# Pr_tica-10.net
KiCad netlist of a schematic drawn in EasyEDA
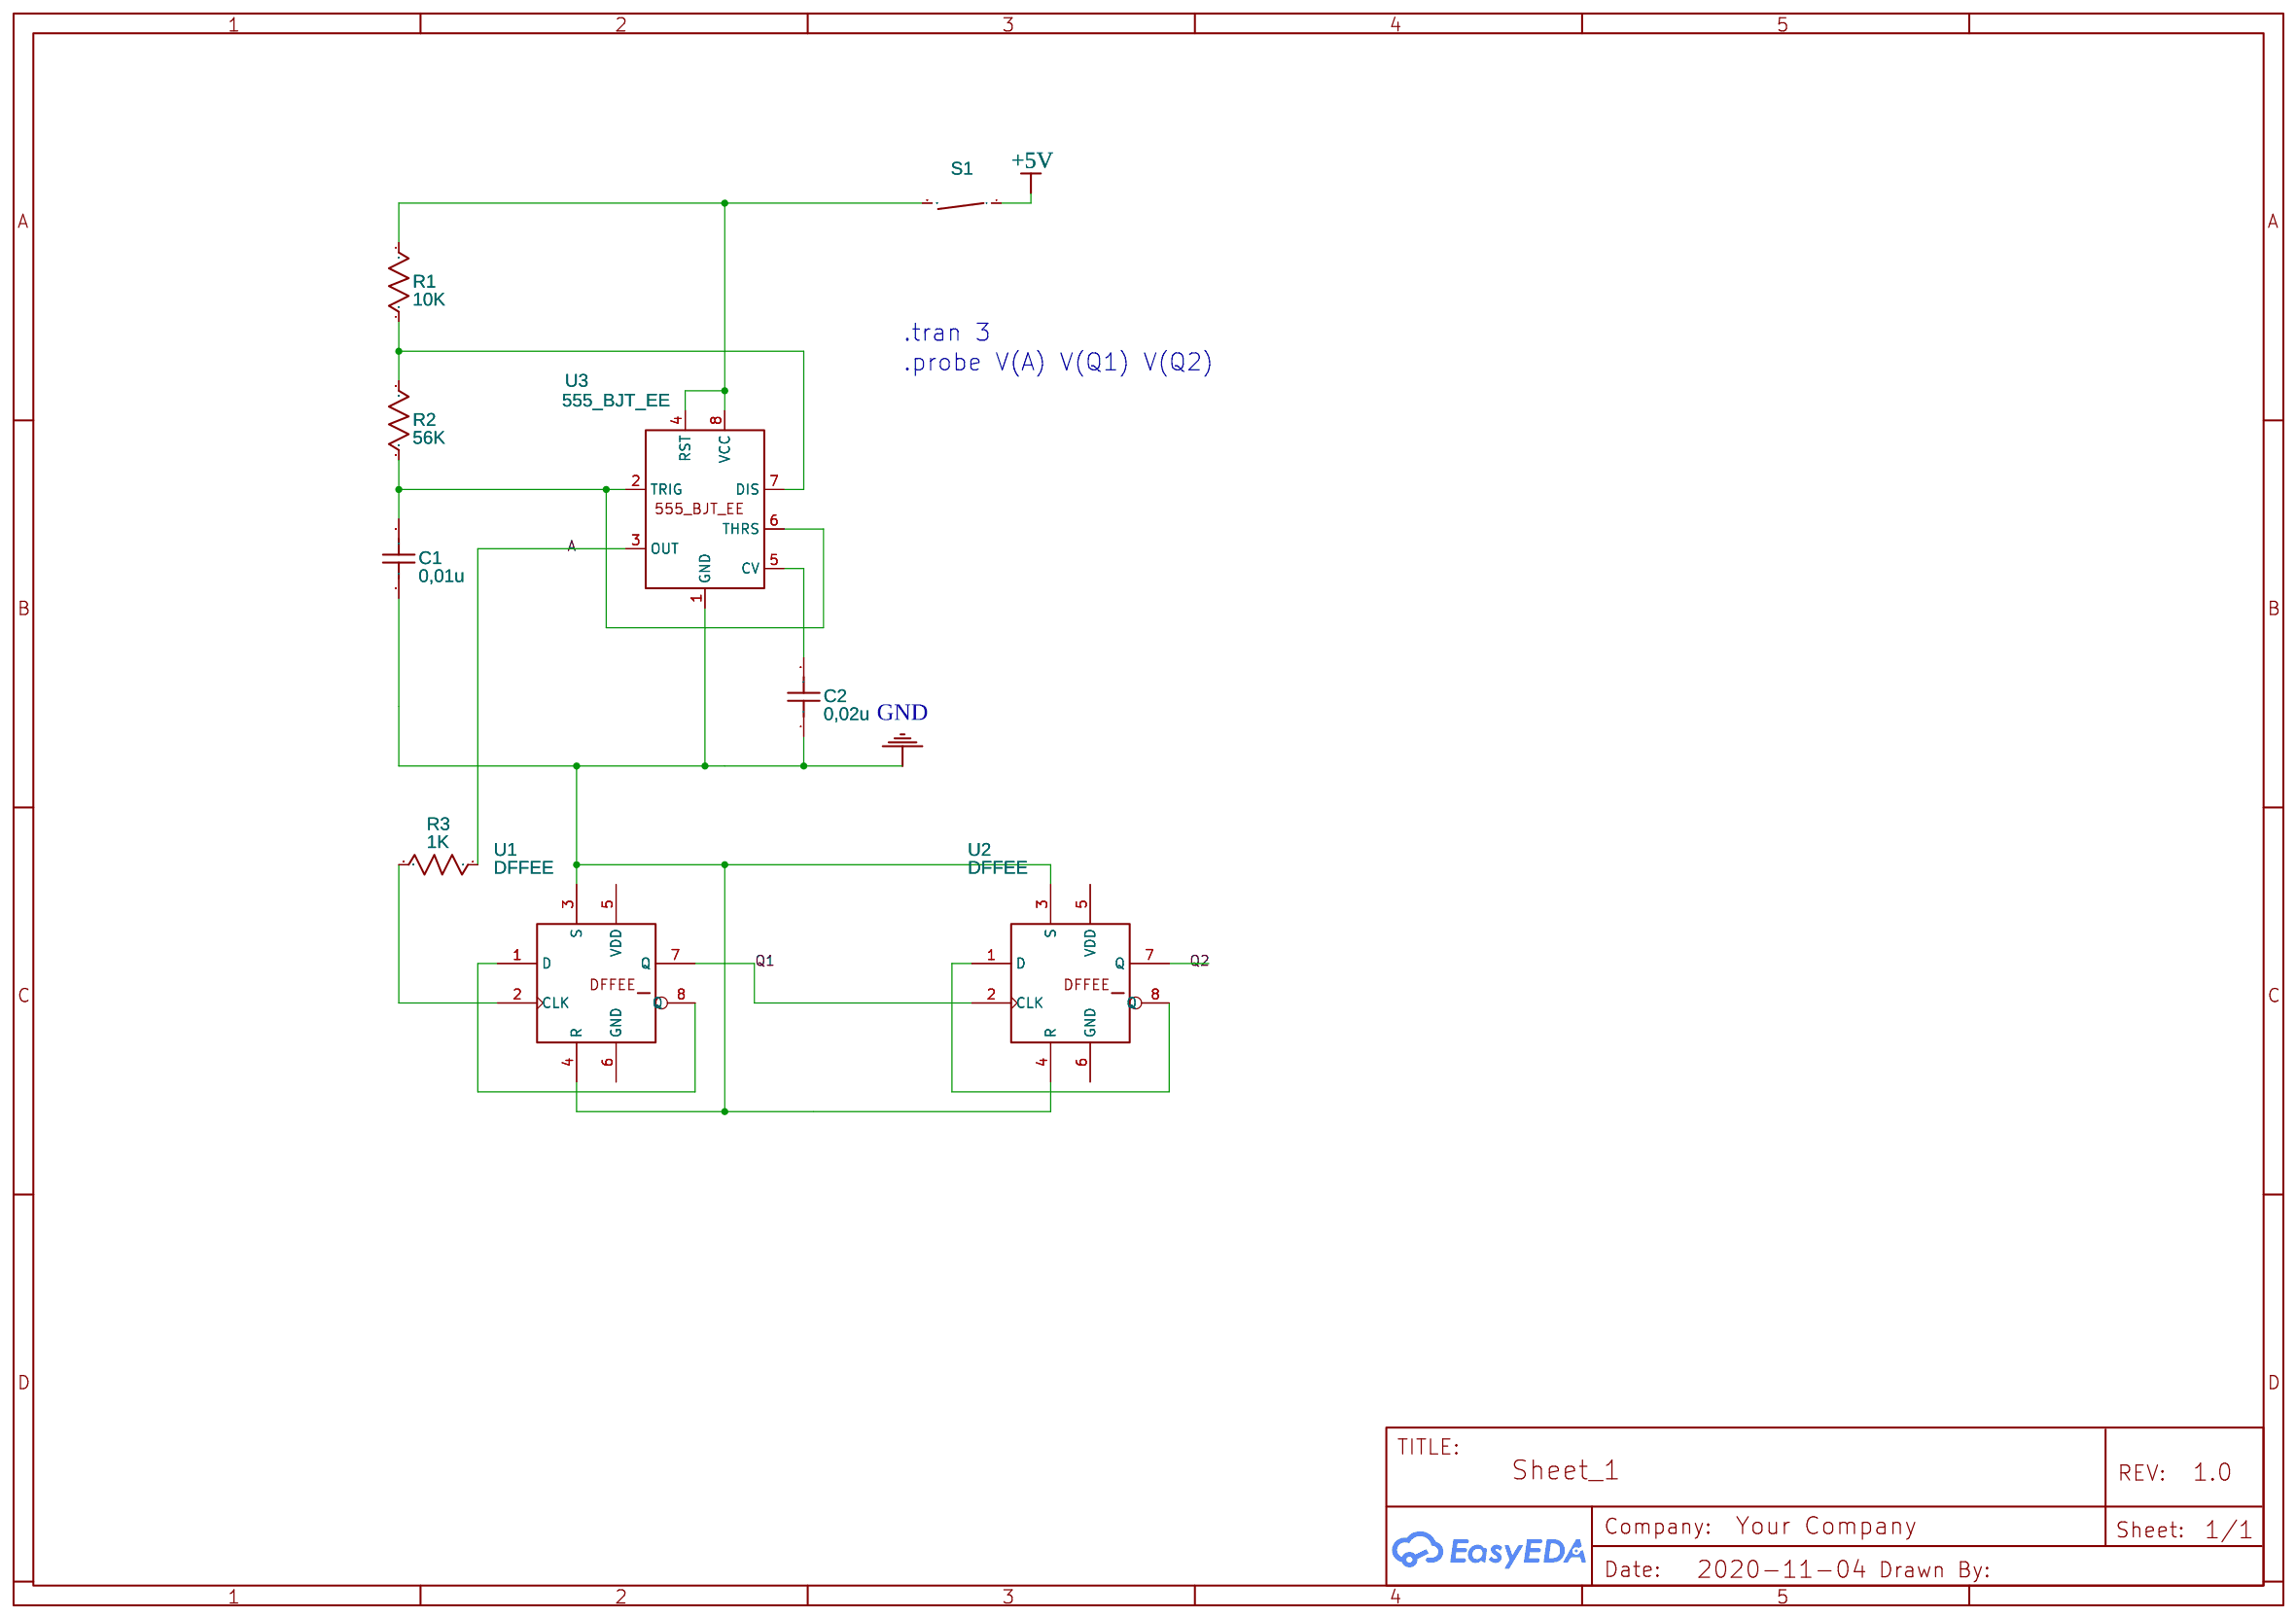
[diagram p0: schematic sheet]

(export (version "E")
  (design (tool "Eeschema 10.0.6"))
  (components
    (comp (ref "C1") (value "0,01u") (libsource (lib "") (part "Capacitor_US")))
    (comp (ref "C2") (value "0,02u") (libsource (lib "") (part "Capacitor_US")))
    (comp (ref "R1") (value "10K") (libsource (lib "") (part "Resistor_US")))
    (comp (ref "R2") (value "56K") (libsource (lib "") (part "Resistor_US")))
    (comp (ref "R3") (value "1K") (libsource (lib "") (part "Resistor_US_1")))
    (comp (ref "S1") (value "SPST_Open") (libsource (lib "") (part "SPST")))
    (comp (ref "U1") (value "DFFEE") (libsource (lib "") (part "LOGIC")))
    (comp (ref "U2") (value "DFFEE") (libsource (lib "") (part "LOGIC")))
    (comp (ref "U3") (value "555_BJT_EE") (libsource (lib "") (part "555_BJT_EE")))
  )
  (nets
    (net (code "1") (name "+5V") (class "Default")
      (node (ref "S1") (pin "1") (pinfunction "1_1") (pintype "unspecified"))
    )
    (net (code "2") (name "/A") (class "Default")
      (node (ref "R3") (pin "1") (pinfunction "1_1") (pintype "unspecified"))
      (node (ref "U3") (pin "3") (pinfunction "OUT_3") (pintype "unspecified"))
    )
    (net (code "3") (name "/Q1") (class "Default")
      (node (ref "U1") (pin "7") (pinfunction "Q_7") (pintype "unspecified"))
      (node (ref "U2") (pin "2") (pinfunction "CLK_2") (pintype "unspecified"))
    )
    (net (code "4") (name "/Q2") (class "Default")
      (node (ref "U2") (pin "7") (pinfunction "Q_7") (pintype "unspecified"))
    )
    (net (code "5") (name "GND") (class "Default")
      (node (ref "C1") (pin "1") (pinfunction "1_1") (pintype "unspecified"))
      (node (ref "C2") (pin "1") (pinfunction "1_1") (pintype "unspecified"))
      (node (ref "U1") (pin "3") (pinfunction "S_3") (pintype "unspecified"))
      (node (ref "U1") (pin "4") (pinfunction "R_4") (pintype "unspecified"))
      (node (ref "U2") (pin "3") (pinfunction "S_3") (pintype "unspecified"))
      (node (ref "U2") (pin "4") (pinfunction "R_4") (pintype "unspecified"))
      (node (ref "U3") (pin "1") (pinfunction "GND_1") (pintype "unspecified"))
    )
    (net (code "6") (name "Net-(U1-CLK)") (class "Default")
      (node (ref "R3") (pin "2") (pinfunction "2_2") (pintype "unspecified"))
      (node (ref "U1") (pin "2") (pinfunction "CLK_2") (pintype "unspecified"))
    )
    (net (code "7") (name "Net-(U1-D)") (class "Default")
      (node (ref "U1") (pin "1") (pinfunction "D_1") (pintype "unspecified"))
      (node (ref "U1") (pin "8") (pinfunction "Q_8") (pintype "unspecified"))
    )
    (net (code "8") (name "Net-(U2-D)") (class "Default")
      (node (ref "U2") (pin "1") (pinfunction "D_1") (pintype "unspecified"))
      (node (ref "U2") (pin "8") (pinfunction "Q_8") (pintype "unspecified"))
    )
    (net (code "9") (name "Net-(U3-CV)") (class "Default")
      (node (ref "C2") (pin "2") (pinfunction "2_2") (pintype "unspecified"))
      (node (ref "U3") (pin "5") (pinfunction "CV_5") (pintype "unspecified"))
    )
    (net (code "10") (name "Net-(U3-DIS)") (class "Default")
      (node (ref "R1") (pin "1") (pinfunction "1_1") (pintype "unspecified"))
      (node (ref "R2") (pin "2") (pinfunction "2_2") (pintype "unspecified"))
      (node (ref "U3") (pin "7") (pinfunction "DIS_7") (pintype "unspecified"))
    )
    (net (code "11") (name "Net-(U3-RST)") (class "Default")
      (node (ref "R1") (pin "2") (pinfunction "2_2") (pintype "unspecified"))
      (node (ref "S1") (pin "2") (pinfunction "2_2") (pintype "unspecified"))
      (node (ref "U3") (pin "4") (pinfunction "RST_4") (pintype "unspecified"))
      (node (ref "U3") (pin "8") (pinfunction "VCC_8") (pintype "unspecified"))
    )
    (net (code "12") (name "Net-(U3-THRS)") (class "Default")
      (node (ref "C1") (pin "2") (pinfunction "2_2") (pintype "unspecified"))
      (node (ref "R2") (pin "1") (pinfunction "1_1") (pintype "unspecified"))
      (node (ref "U3") (pin "2") (pinfunction "TRIG_2") (pintype "unspecified"))
      (node (ref "U3") (pin "6") (pinfunction "THRS_6") (pintype "unspecified"))
    )
    (net (code "13") (name "unconnected-(U1-GND-Pad6)") (class "Default")
      (node (ref "U1") (pin "6") (pinfunction "GND_6") (pintype "unspecified"))
    )
    (net (code "14") (name "unconnected-(U1-VDD-Pad5)") (class "Default")
      (node (ref "U1") (pin "5") (pinfunction "VDD_5") (pintype "unspecified"))
    )
    (net (code "15") (name "unconnected-(U2-GND-Pad6)") (class "Default")
      (node (ref "U2") (pin "6") (pinfunction "GND_6") (pintype "unspecified"))
    )
    (net (code "16") (name "unconnected-(U2-VDD-Pad5)") (class "Default")
      (node (ref "U2") (pin "5") (pinfunction "VDD_5") (pintype "unspecified"))
    )
  )
)
